# main.net
KiCad netlist of a schematic drawn in Altium Designer
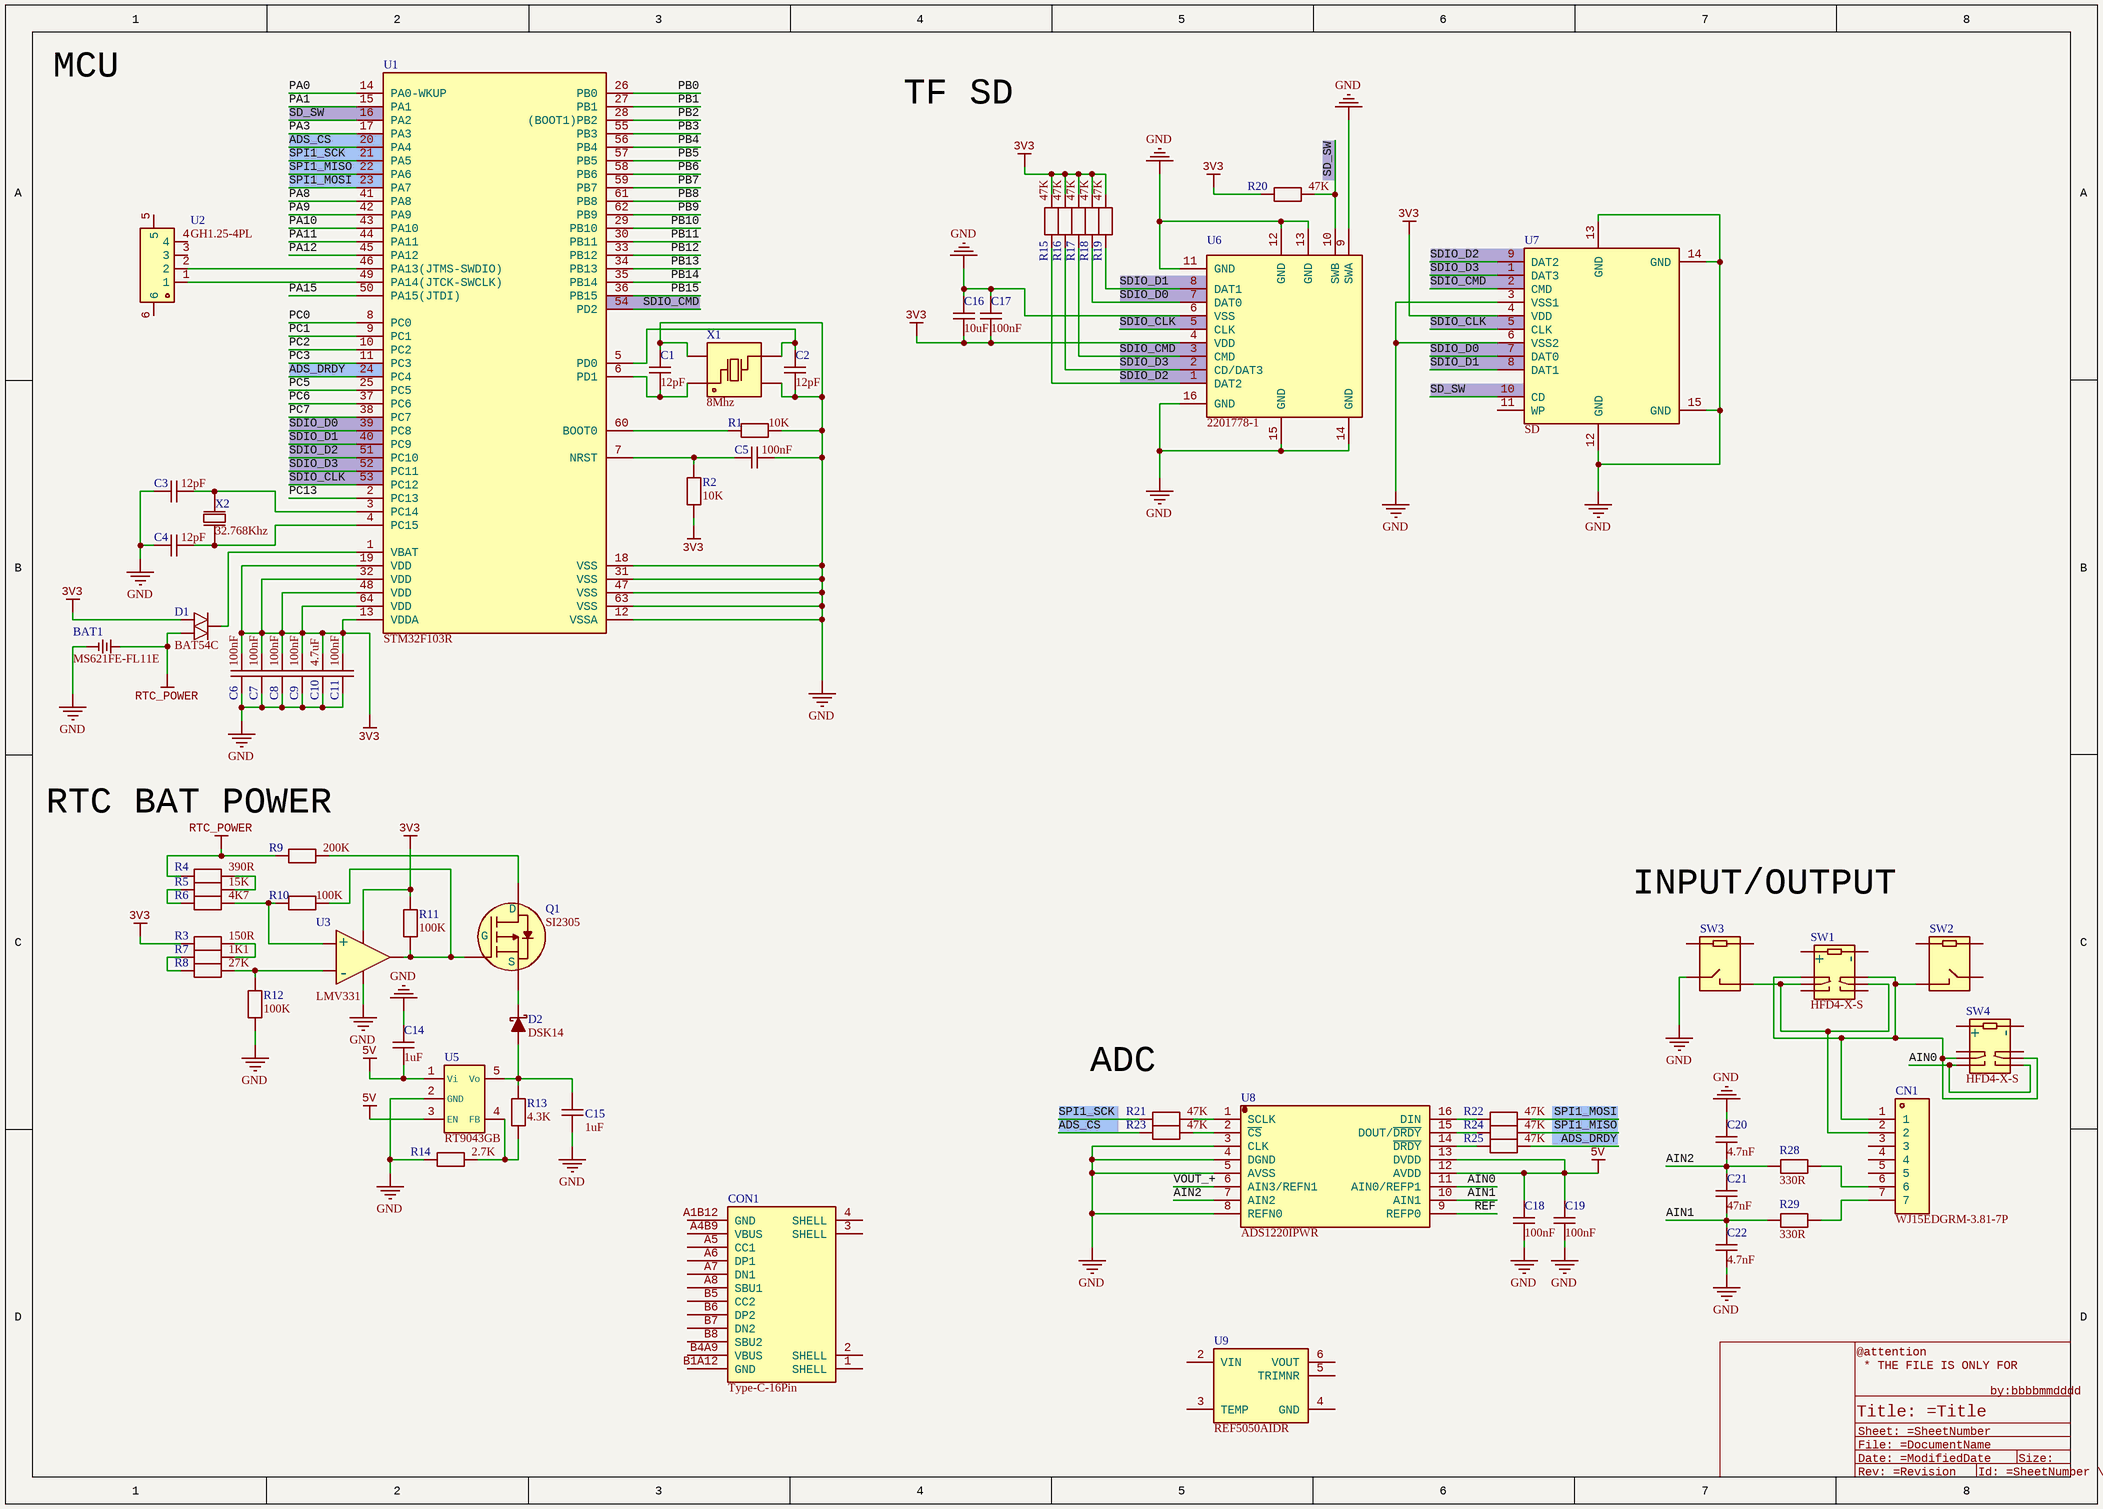
[diagram p0: main.SchDoc]

(export (version "E")
  (design (tool "Eeschema 10.0.6"))
  (components
    (comp (ref "BAT1")
      (value "MS621FE-FL11E")
      (footprint "SMD_FL11E")
      (libsource (lib "STM32") (part "MS621FE-FL11E"))
    )
    (comp (ref "C1") (value "12pF") (footprint "C_0402") (libsource (lib "STM32") (part "C_MLCC")))
    (comp (ref "C2") (value "12pF") (footprint "C_0402") (libsource (lib "STM32") (part "C_MLCC")))
    (comp (ref "C3") (value "12pF") (footprint "C_0402") (libsource (lib "STM32") (part "C_MLCC")))
    (comp (ref "C4") (value "12pF") (footprint "C_0402") (libsource (lib "STM32") (part "C_MLCC")))
    (comp (ref "C5") (value "100nF") (footprint "C_0402") (libsource (lib "STM32") (part "C_MLCC")))
    (comp (ref "C6") (value "100nF") (footprint "C_0603") (libsource (lib "STM32") (part "C_MLCC")))
    (comp (ref "C7") (value "100nF") (footprint "C_0603") (libsource (lib "STM32") (part "C_MLCC")))
    (comp (ref "C8") (value "100nF") (footprint "C_0603") (libsource (lib "STM32") (part "C_MLCC")))
    (comp (ref "C9") (value "100nF") (footprint "C_0603") (libsource (lib "STM32") (part "C_MLCC")))
    (comp (ref "C10") (value "4.7uF") (footprint "C_0603") (libsource (lib "STM32") (part "C_MLCC")))
    (comp (ref "C11") (value "100nF") (footprint "C_0603") (libsource (lib "STM32") (part "C_MLCC")))
    (comp (ref "C14") (value "1uF") (footprint "C_0603") (libsource (lib "STM32") (part "C_MLCC")))
    (comp (ref "C15") (value "1uF") (footprint "C_0603") (libsource (lib "STM32") (part "C_MLCC")))
    (comp (ref "C16") (value "10uF") (footprint "C_0603") (libsource (lib "STM32") (part "C_MLCC")))
    (comp (ref "C17") (value "100nF") (footprint "C_0402") (libsource (lib "STM32") (part "C_MLCC")))
    (comp (ref "C18") (value "100nF") (footprint "C_0805") (libsource (lib "STM32") (part "C_MLCC")))
    (comp (ref "C19") (value "100nF") (footprint "C_0805") (libsource (lib "STM32") (part "C_MLCC")))
    (comp (ref "C20") (value "4.7nF") (footprint "C_0603") (libsource (lib "STM32") (part "C_MLCC")))
    (comp (ref "C21") (value "47nF") (footprint "C_0603") (libsource (lib "STM32") (part "C_MLCC")))
    (comp (ref "C22") (value "4.7nF") (footprint "C_0603") (libsource (lib "STM32") (part "C_MLCC")))
    (comp (ref "CN1")
      (value "WJ15EDGRM-3.81-7P")
      (footprint "WJ15EDGRM-3.81-7P")
      (libsource (lib "STM32") (part "WJ15EDGRM-3.81-7P"))
    )
    (comp (ref "CON1")
      (value "Type-C-16Pin")
      (footprint "Type-C-16Pin")
      (libsource (lib "STM32") (part "Type-C-16Pin"))
    )
    (comp (ref "D1")
      (value "BAT54C")
      (footprint "SOT-23")
      (description "SOT-23")
      (libsource (lib "STM32") (part "BAT54C"))
    )
    (comp (ref "D2") (value "DSK14") (footprint "SOD-123FL") (libsource (lib "STM32") (part "DSK14")))
    (comp (ref "Q1")
      (value "SI2305")
      (footprint "SOT-23")
      (description "p-mos")
      (libsource (lib "STM32") (part "SI2305"))
    )
    (comp (ref "R1") (value "10K") (footprint "R_0402") (libsource (lib "STM32") (part "R_SMD")))
    (comp (ref "R2") (value "10K") (footprint "R_0402") (libsource (lib "STM32") (part "R_SMD")))
    (comp (ref "R3") (value "150R") (footprint "R_0402") (libsource (lib "STM32") (part "R_SMD")))
    (comp (ref "R4") (value "390R") (footprint "R_0402") (libsource (lib "STM32") (part "R_SMD")))
    (comp (ref "R5") (value "15K") (footprint "R_0402") (libsource (lib "STM32") (part "R_SMD")))
    (comp (ref "R6") (value "4K7") (footprint "R_0402") (libsource (lib "STM32") (part "R_SMD")))
    (comp (ref "R7") (value "1K1") (footprint "R_0402") (libsource (lib "STM32") (part "R_SMD")))
    (comp (ref "R8") (value "27K") (footprint "R_0402") (libsource (lib "STM32") (part "R_SMD")))
    (comp (ref "R9") (value "200K") (footprint "R_0402") (libsource (lib "STM32") (part "R_SMD")))
    (comp (ref "R10") (value "100K") (footprint "R_0402") (libsource (lib "STM32") (part "R_SMD")))
    (comp (ref "R11") (value "100K") (footprint "R_0402") (libsource (lib "STM32") (part "R_SMD")))
    (comp (ref "R12") (value "100K") (footprint "R_0402") (libsource (lib "STM32") (part "R_SMD")))
    (comp (ref "R13") (value "4.3K") (footprint "R_0402") (libsource (lib "STM32") (part "R_SMD")))
    (comp (ref "R14") (value "2.7K") (footprint "R_0402") (libsource (lib "STM32") (part "R_SMD")))
    (comp (ref "R15") (value "47K") (footprint "R_0402") (libsource (lib "STM32") (part "R_SMD")))
    (comp (ref "R16") (value "47K") (footprint "R_0402") (libsource (lib "STM32") (part "R_SMD")))
    (comp (ref "R17") (value "47K") (footprint "R_0402") (libsource (lib "STM32") (part "R_SMD")))
    (comp (ref "R18") (value "47K") (footprint "R_0402") (libsource (lib "STM32") (part "R_SMD")))
    (comp (ref "R19") (value "47K") (footprint "R_0402") (libsource (lib "STM32") (part "R_SMD")))
    (comp (ref "R20") (value "47K") (footprint "R_0402") (libsource (lib "STM32") (part "R_SMD")))
    (comp (ref "R21") (value "47K") (footprint "R_0402") (libsource (lib "STM32") (part "R_SMD")))
    (comp (ref "R22") (value "47K") (footprint "R_0402") (libsource (lib "STM32") (part "R_SMD")))
    (comp (ref "R23") (value "47K") (footprint "R_0402") (libsource (lib "STM32") (part "R_SMD")))
    (comp (ref "R24") (value "47K") (footprint "R_0402") (libsource (lib "STM32") (part "R_SMD")))
    (comp (ref "R25") (value "47K") (footprint "R_0402") (libsource (lib "STM32") (part "R_SMD")))
    (comp (ref "R28") (value "330R") (footprint "R_0603") (libsource (lib "STM32") (part "R_SMD")))
    (comp (ref "R29") (value "330R") (footprint "R_0603") (libsource (lib "STM32") (part "R_SMD")))
    (comp (ref "SW1")
      (value "HFD4-X-S")
      (footprint "HFD4-X-S")
      (description "继电器")
      (libsource (lib "STM32") (part "HFD4-X-S"))
    )
    (comp (ref "SW2")
      (value "HF32FV-16/5-HLTF(590)")
      (footprint "HF32FV-16/5-HLTF(590)")
      (description "继电器")
      (libsource (lib "STM32") (part "HF32FV-16/5-HLTF(590)"))
    )
    (comp (ref "SW3")
      (value "HF32FV-16/5-HLTF(590)")
      (footprint "HF32FV-16/5-HLTF(590)")
      (description "继电器")
      (libsource (lib "") (part "HF32FV-16/5-HLTF(590)_1"))
    )
    (comp (ref "SW4")
      (value "HFD4-X-S")
      (footprint "HFD4-X-S")
      (description "继电器")
      (libsource (lib "STM32") (part "HFD4-X-S"))
    )
    (comp (ref "U1")
      (value "STM32F103R")
      (footprint "LQFP_64")
      (description "64-pin LQFP")
      (libsource (lib "STM32") (part "STM32F103Rx"))
    )
    (comp (ref "U2")
      (value "GH1.25-4PL")
      (footprint "GH1.25-4PL")
      (libsource (lib "STM32") (part "GH1.25-4PL"))
    )
    (comp (ref "U3")
      (value "LMV331")
      (footprint "SOT-23-5P")
      (description "LMV331IDBVR")
      (libsource (lib "STM32") (part "LMV331IDBVR"))
    )
    (comp (ref "U5")
      (value "RT9043GB")
      (footprint "SOT-23-5P")
      (description "LDO")
      (libsource (lib "STM32") (part "RT9043GB"))
    )
    (comp (ref "U6")
      (value "2201778-1")
      (footprint "2201778-1")
      (description "TF卡槽")
      (libsource (lib "STM32") (part "2201778-1"))
    )
    (comp (ref "U7")
      (value "SD")
      (footprint "SMD_SD-102")
      (description "长体SD卡槽")
      (libsource (lib "STM32") (part "长体SD卡槽"))
    )
    (comp (ref "U8")
      (value "ADS1220IPWR")
      (footprint "TSSOP-16")
      (description "24Bit ADC")
      (libsource (lib "STM32") (part "ADS1220IPWR"))
    )
    (comp (ref "U9")
      (value "REF5050AIDR")
      (footprint "SOIC-8")
      (libsource (lib "STM32") (part "REF5050AIDR"))
    )
    (comp (ref "X1")
      (value "8Mhz")
      (footprint "SMD3225-4P")
      (libsource (lib "STM32") (part "Crystal_SMD3225-4P"))
    )
    (comp (ref "X2")
      (value "32.768Khz")
      (footprint "SMD3215-2P")
      (libsource (lib "STM32") (part "Crystal_3215-2P"))
    )
  )
  (nets
    (net (code "1") (name "/ADS_CS") (class "Default")
      (node (ref "R23") (pin "1") (pinfunction "1_1") (pintype "passive"))
      (node (ref "U1") (pin "20") (pinfunction "PA4_20") (pintype "passive"))
    )
    (net (code "2") (name "/ADS_DRDY") (class "Default")
      (node (ref "R25") (pin "2") (pinfunction "2_2") (pintype "passive"))
      (node (ref "U1") (pin "24") (pinfunction "PC4_24") (pintype "passive"))
    )
    (net (code "3") (name "/AIN0") (class "Default")
      (node (ref "SW4") (pin "4") (pinfunction "4_4") (pintype "passive"))
      (node (ref "SW4") (pin "5") (pinfunction "5_5") (pintype "passive"))
      (node (ref "U8") (pin "11") (pinfunction "AIN0/REFP1_11") (pintype "passive"))
    )
    (net (code "4") (name "/AIN1") (class "Default")
      (node (ref "C21") (pin "2") (pinfunction "2_2") (pintype "passive"))
      (node (ref "C22") (pin "1") (pinfunction "1_1") (pintype "passive"))
      (node (ref "R29") (pin "1") (pinfunction "1_1") (pintype "passive"))
      (node (ref "U8") (pin "10") (pinfunction "AIN1_10") (pintype "passive"))
    )
    (net (code "5") (name "/AIN2") (class "Default")
      (node (ref "C20") (pin "2") (pinfunction "2_2") (pintype "passive"))
      (node (ref "C21") (pin "1") (pinfunction "1_1") (pintype "passive"))
      (node (ref "R28") (pin "1") (pinfunction "1_1") (pintype "passive"))
      (node (ref "U8") (pin "7") (pinfunction "AIN2_7") (pintype "passive"))
    )
    (net (code "6") (name "/PA0") (class "Default")
      (node (ref "U1") (pin "14") (pinfunction "PA0-WKUP_14") (pintype "passive"))
    )
    (net (code "7") (name "/PA1") (class "Default")
      (node (ref "U1") (pin "15") (pinfunction "PA1_15") (pintype "passive"))
    )
    (net (code "8") (name "/PA3") (class "Default")
      (node (ref "U1") (pin "17") (pinfunction "PA3_17") (pintype "passive"))
    )
    (net (code "9") (name "/PA8") (class "Default")
      (node (ref "U1") (pin "41") (pinfunction "PA8_41") (pintype "passive"))
    )
    (net (code "10") (name "/PA9") (class "Default")
      (node (ref "U1") (pin "42") (pinfunction "PA9_42") (pintype "passive"))
    )
    (net (code "11") (name "/PA10") (class "Default")
      (node (ref "U1") (pin "43") (pinfunction "PA10_43") (pintype "passive"))
    )
    (net (code "12") (name "/PA11") (class "Default")
      (node (ref "U1") (pin "44") (pinfunction "PA11_44") (pintype "passive"))
    )
    (net (code "13") (name "/PA12") (class "Default")
      (node (ref "U1") (pin "45") (pinfunction "PA12_45") (pintype "passive"))
    )
    (net (code "14") (name "/PA15") (class "Default")
      (node (ref "U1") (pin "50") (pinfunction "PA15(JTDI)_50") (pintype "passive"))
    )
    (net (code "15") (name "/PB0") (class "Default")
      (node (ref "U1") (pin "26") (pinfunction "PB0_26") (pintype "passive"))
    )
    (net (code "16") (name "/PB1") (class "Default")
      (node (ref "U1") (pin "27") (pinfunction "PB1_27") (pintype "passive"))
    )
    (net (code "17") (name "/PB2") (class "Default")
      (node (ref "U1") (pin "28") (pinfunction "(BOOT1)PB2_28") (pintype "passive"))
    )
    (net (code "18") (name "/PB3") (class "Default")
      (node (ref "U1") (pin "55") (pinfunction "PB3_55") (pintype "passive"))
    )
    (net (code "19") (name "/PB4") (class "Default")
      (node (ref "U1") (pin "56") (pinfunction "PB4_56") (pintype "passive"))
    )
    (net (code "20") (name "/PB5") (class "Default")
      (node (ref "U1") (pin "57") (pinfunction "PB5_57") (pintype "passive"))
    )
    (net (code "21") (name "/PB6") (class "Default")
      (node (ref "U1") (pin "58") (pinfunction "PB6_58") (pintype "passive"))
    )
    (net (code "22") (name "/PB7") (class "Default")
      (node (ref "U1") (pin "59") (pinfunction "PB7_59") (pintype "passive"))
    )
    (net (code "23") (name "/PB8") (class "Default")
      (node (ref "U1") (pin "61") (pinfunction "PB8_61") (pintype "passive"))
    )
    (net (code "24") (name "/PB9") (class "Default")
      (node (ref "U1") (pin "62") (pinfunction "PB9_62") (pintype "passive"))
    )
    (net (code "25") (name "/PB10") (class "Default")
      (node (ref "U1") (pin "29") (pinfunction "PB10_29") (pintype "passive"))
    )
    (net (code "26") (name "/PB11") (class "Default")
      (node (ref "U1") (pin "30") (pinfunction "PB11_30") (pintype "passive"))
    )
    (net (code "27") (name "/PB12") (class "Default")
      (node (ref "U1") (pin "33") (pinfunction "PB12_33") (pintype "passive"))
    )
    (net (code "28") (name "/PB13") (class "Default")
      (node (ref "U1") (pin "34") (pinfunction "PB13_34") (pintype "passive"))
    )
    (net (code "29") (name "/PB14") (class "Default")
      (node (ref "U1") (pin "35") (pinfunction "PB14_35") (pintype "passive"))
    )
    (net (code "30") (name "/PB15") (class "Default")
      (node (ref "U1") (pin "36") (pinfunction "PB15_36") (pintype "passive"))
    )
    (net (code "31") (name "/PC0") (class "Default")
      (node (ref "U1") (pin "8") (pinfunction "PC0_8") (pintype "passive"))
    )
    (net (code "32") (name "/PC1") (class "Default")
      (node (ref "U1") (pin "9") (pinfunction "PC1_9") (pintype "passive"))
    )
    (net (code "33") (name "/PC2") (class "Default")
      (node (ref "U1") (pin "10") (pinfunction "PC2_10") (pintype "passive"))
    )
    (net (code "34") (name "/PC3") (class "Default")
      (node (ref "U1") (pin "11") (pinfunction "PC3_11") (pintype "passive"))
    )
    (net (code "35") (name "/PC5") (class "Default")
      (node (ref "U1") (pin "25") (pinfunction "PC5_25") (pintype "passive"))
    )
    (net (code "36") (name "/PC6") (class "Default")
      (node (ref "U1") (pin "37") (pinfunction "PC6_37") (pintype "passive"))
    )
    (net (code "37") (name "/PC7") (class "Default")
      (node (ref "U1") (pin "38") (pinfunction "PC7_38") (pintype "passive"))
    )
    (net (code "38") (name "/PC13") (class "Default")
      (node (ref "U1") (pin "2") (pinfunction "PC13_2") (pintype "passive"))
    )
    (net (code "39") (name "/REF") (class "Default")
      (node (ref "U8") (pin "9") (pinfunction "REFP0_9") (pintype "passive"))
    )
    (net (code "40") (name "/SDIO_CLK") (class "Default")
      (node (ref "U1") (pin "53") (pinfunction "PC12_53") (pintype "passive"))
      (node (ref "U6") (pin "5") (pinfunction "CLK_5") (pintype "passive"))
      (node (ref "U7") (pin "5") (pinfunction "CLK_5") (pintype "passive"))
    )
    (net (code "41") (name "/SDIO_CMD") (class "Default")
      (node (ref "R17") (pin "1") (pinfunction "1_1") (pintype "passive"))
      (node (ref "U1") (pin "54") (pinfunction "PD2_54") (pintype "passive"))
      (node (ref "U6") (pin "3") (pinfunction "CMD_3") (pintype "passive"))
      (node (ref "U7") (pin "2") (pinfunction "CMD_2") (pintype "passive"))
    )
    (net (code "42") (name "/SDIO_D0") (class "Default")
      (node (ref "R18") (pin "1") (pinfunction "1_1") (pintype "passive"))
      (node (ref "U1") (pin "39") (pinfunction "PC8_39") (pintype "passive"))
      (node (ref "U6") (pin "7") (pinfunction "DAT0_7") (pintype "passive"))
      (node (ref "U7") (pin "7") (pinfunction "DAT0_7") (pintype "passive"))
    )
    (net (code "43") (name "/SDIO_D1") (class "Default")
      (node (ref "R19") (pin "1") (pinfunction "1_1") (pintype "passive"))
      (node (ref "U1") (pin "40") (pinfunction "PC9_40") (pintype "passive"))
      (node (ref "U6") (pin "8") (pinfunction "DAT1_8") (pintype "passive"))
      (node (ref "U7") (pin "8") (pinfunction "DAT1_8") (pintype "passive"))
    )
    (net (code "44") (name "/SDIO_D2") (class "Default")
      (node (ref "R15") (pin "1") (pinfunction "1_1") (pintype "passive"))
      (node (ref "U1") (pin "51") (pinfunction "PC10_51") (pintype "passive"))
      (node (ref "U6") (pin "1") (pinfunction "DAT2_1") (pintype "passive"))
      (node (ref "U7") (pin "9") (pinfunction "DAT2_9") (pintype "passive"))
    )
    (net (code "45") (name "/SDIO_D3") (class "Default")
      (node (ref "R16") (pin "1") (pinfunction "1_1") (pintype "passive"))
      (node (ref "U1") (pin "52") (pinfunction "PC11_52") (pintype "passive"))
      (node (ref "U6") (pin "2") (pinfunction "CD/DAT3_2") (pintype "passive"))
      (node (ref "U7") (pin "1") (pinfunction "DAT3_1") (pintype "passive"))
    )
    (net (code "46") (name "/SD_SW") (class "Default")
      (node (ref "R20") (pin "1") (pinfunction "1_1") (pintype "passive"))
      (node (ref "U1") (pin "16") (pinfunction "PA2_16") (pintype "passive"))
      (node (ref "U6") (pin "10") (pinfunction "SWB_10") (pintype "passive"))
      (node (ref "U7") (pin "10") (pinfunction "CD_10") (pintype "passive"))
    )
    (net (code "47") (name "/SPI1_MISO") (class "Default")
      (node (ref "R24") (pin "2") (pinfunction "2_2") (pintype "passive"))
      (node (ref "U1") (pin "22") (pinfunction "PA6_22") (pintype "passive"))
    )
    (net (code "48") (name "/SPI1_MOSI") (class "Default")
      (node (ref "R22") (pin "2") (pinfunction "2_2") (pintype "passive"))
      (node (ref "U1") (pin "23") (pinfunction "PA7_23") (pintype "passive"))
    )
    (net (code "49") (name "/SPI1_SCK") (class "Default")
      (node (ref "R21") (pin "1") (pinfunction "1_1") (pintype "passive"))
      (node (ref "U1") (pin "21") (pinfunction "PA5_21") (pintype "passive"))
    )
    (net (code "50") (name "/VOUT_+") (class "Default")
      (node (ref "U8") (pin "6") (pinfunction "AIN3/REFN1_6") (pintype "passive"))
    )
    (net (code "51") (name "3V3") (class "Default")
      (node (ref "C10") (pin "1") (pinfunction "1_1") (pintype "passive"))
      (node (ref "C11") (pin "1") (pinfunction "1_1") (pintype "passive"))
      (node (ref "C16") (pin "1") (pinfunction "1_1") (pintype "passive"))
      (node (ref "C17") (pin "1") (pinfunction "1_1") (pintype "passive"))
      (node (ref "C6") (pin "1") (pinfunction "1_1") (pintype "passive"))
      (node (ref "C7") (pin "1") (pinfunction "1_1") (pintype "passive"))
      (node (ref "C8") (pin "1") (pinfunction "1_1") (pintype "passive"))
      (node (ref "C9") (pin "1") (pinfunction "1_1") (pintype "passive"))
      (node (ref "D1") (pin "1") (pinfunction "1_1") (pintype "passive"))
      (node (ref "R11") (pin "2") (pinfunction "2_2") (pintype "passive"))
      (node (ref "R15") (pin "2") (pinfunction "2_2") (pintype "passive"))
      (node (ref "R16") (pin "2") (pinfunction "2_2") (pintype "passive"))
      (node (ref "R17") (pin "2") (pinfunction "2_2") (pintype "passive"))
      (node (ref "R18") (pin "2") (pinfunction "2_2") (pintype "passive"))
      (node (ref "R19") (pin "2") (pinfunction "2_2") (pintype "passive"))
      (node (ref "R2") (pin "2") (pinfunction "2_2") (pintype "passive"))
      (node (ref "R20") (pin "2") (pinfunction "2_2") (pintype "passive"))
      (node (ref "R3") (pin "1") (pinfunction "1_1") (pintype "passive"))
      (node (ref "U1") (pin "13") (pinfunction "VDDA_13") (pintype "passive"))
      (node (ref "U1") (pin "19") (pinfunction "VDD_19") (pintype "passive"))
      (node (ref "U1") (pin "32") (pinfunction "VDD_32") (pintype "passive"))
      (node (ref "U1") (pin "48") (pinfunction "VDD_48") (pintype "passive"))
      (node (ref "U1") (pin "64") (pinfunction "VDD_64") (pintype "passive"))
      (node (ref "U3") (pin "5") (pinfunction "5_5") (pintype "passive"))
      (node (ref "U6") (pin "4") (pinfunction "VDD_4") (pintype "passive"))
      (node (ref "U7") (pin "4") (pinfunction "VDD_4") (pintype "passive"))
    )
    (net (code "52") (name "5V") (class "Default")
      (node (ref "C14") (pin "2") (pinfunction "2_2") (pintype "passive"))
      (node (ref "C18") (pin "1") (pinfunction "1_1") (pintype "passive"))
      (node (ref "C19") (pin "1") (pinfunction "1_1") (pintype "passive"))
      (node (ref "U5") (pin "1") (pinfunction "Vi_1") (pintype "passive"))
      (node (ref "U5") (pin "3") (pinfunction "EN_3") (pintype "passive"))
      (node (ref "U8") (pin "12") (pinfunction "AVDD_12") (pintype "passive"))
      (node (ref "U8") (pin "13") (pinfunction "DVDD_13") (pintype "passive"))
    )
    (net (code "53") (name "GND") (class "Default")
      (node (ref "BAT1") (pin "2") (pinfunction "2_2") (pintype "passive"))
      (node (ref "C1") (pin "2") (pinfunction "2_2") (pintype "passive"))
      (node (ref "C10") (pin "2") (pinfunction "2_2") (pintype "passive"))
      (node (ref "C11") (pin "2") (pinfunction "2_2") (pintype "passive"))
      (node (ref "C14") (pin "1") (pinfunction "1_1") (pintype "passive"))
      (node (ref "C15") (pin "1") (pinfunction "1_1") (pintype "passive"))
      (node (ref "C16") (pin "2") (pinfunction "2_2") (pintype "passive"))
      (node (ref "C17") (pin "2") (pinfunction "2_2") (pintype "passive"))
      (node (ref "C18") (pin "2") (pinfunction "2_2") (pintype "passive"))
      (node (ref "C19") (pin "2") (pinfunction "2_2") (pintype "passive"))
      (node (ref "C2") (pin "1") (pinfunction "1_1") (pintype "passive"))
      (node (ref "C20") (pin "1") (pinfunction "1_1") (pintype "passive"))
      (node (ref "C22") (pin "2") (pinfunction "2_2") (pintype "passive"))
      (node (ref "C3") (pin "1") (pinfunction "1_1") (pintype "passive"))
      (node (ref "C4") (pin "1") (pinfunction "1_1") (pintype "passive"))
      (node (ref "C5") (pin "2") (pinfunction "2_2") (pintype "passive"))
      (node (ref "C6") (pin "2") (pinfunction "2_2") (pintype "passive"))
      (node (ref "C7") (pin "2") (pinfunction "2_2") (pintype "passive"))
      (node (ref "C8") (pin "2") (pinfunction "2_2") (pintype "passive"))
      (node (ref "C9") (pin "2") (pinfunction "2_2") (pintype "passive"))
      (node (ref "R1") (pin "2") (pinfunction "2_2") (pintype "passive"))
      (node (ref "R12") (pin "1") (pinfunction "1_1") (pintype "passive"))
      (node (ref "R14") (pin "2") (pinfunction "2_2") (pintype "passive"))
      (node (ref "SW3") (pin "4") (pinfunction "4_4") (pintype "passive"))
      (node (ref "U1") (pin "12") (pinfunction "VSSA_12") (pintype "passive"))
      (node (ref "U1") (pin "18") (pinfunction "VSS_18") (pintype "passive"))
      (node (ref "U1") (pin "31") (pinfunction "VSS_31") (pintype "passive"))
      (node (ref "U1") (pin "47") (pinfunction "VSS_47") (pintype "passive"))
      (node (ref "U1") (pin "63") (pinfunction "VSS_63") (pintype "passive"))
      (node (ref "U3") (pin "2") (pinfunction "2_2") (pintype "passive"))
      (node (ref "U5") (pin "2") (pinfunction "GND_2") (pintype "passive"))
      (node (ref "U6") (pin "11") (pinfunction "GND_11") (pintype "passive"))
      (node (ref "U6") (pin "12") (pinfunction "GND_12") (pintype "passive"))
      (node (ref "U6") (pin "13") (pinfunction "GND_13") (pintype "passive"))
      (node (ref "U6") (pin "14") (pinfunction "GND_14") (pintype "passive"))
      (node (ref "U6") (pin "15") (pinfunction "GND_15") (pintype "passive"))
      (node (ref "U6") (pin "16") (pinfunction "GND_16") (pintype "passive"))
      (node (ref "U6") (pin "6") (pinfunction "VSS_6") (pintype "passive"))
      (node (ref "U6") (pin "9") (pinfunction "SWA_9") (pintype "passive"))
      (node (ref "U7") (pin "12") (pinfunction "GND_12") (pintype "passive"))
      (node (ref "U7") (pin "13") (pinfunction "GND_13") (pintype "passive"))
      (node (ref "U7") (pin "14") (pinfunction "GND_14") (pintype "passive"))
      (node (ref "U7") (pin "15") (pinfunction "GND_15") (pintype "passive"))
      (node (ref "U7") (pin "3") (pinfunction "VSS1_3") (pintype "passive"))
      (node (ref "U7") (pin "6") (pinfunction "VSS2_6") (pintype "passive"))
      (node (ref "U8") (pin "3") (pinfunction "CLK_3") (pintype "passive"))
      (node (ref "U8") (pin "4") (pinfunction "DGND_4") (pintype "passive"))
      (node (ref "U8") (pin "5") (pinfunction "AVSS_5") (pintype "passive"))
      (node (ref "U8") (pin "8") (pinfunction "REFN0_8") (pintype "passive"))
      (node (ref "X1") (pin "2") (pinfunction "2_2") (pintype "passive"))
      (node (ref "X1") (pin "4") (pinfunction "4_4") (pintype "passive"))
    )
    (net (code "54") (name "Net-(CN1-Pad1)") (class "Default")
      (node (ref "CN1") (pin "1") (pinfunction "1_1") (pintype "passive"))
      (node (ref "SW1") (pin "2") (pinfunction "2_2") (pintype "passive"))
      (node (ref "SW1") (pin "7") (pinfunction "7_7") (pintype "passive"))
      (node (ref "SW2") (pin "3") (pinfunction "3_3") (pintype "passive"))
      (node (ref "SW4") (pin "3") (pinfunction "3_3") (pintype "passive"))
      (node (ref "SW4") (pin "6") (pinfunction "6_6") (pintype "passive"))
    )
    (net (code "55") (name "Net-(CN1-Pad2)") (class "Default")
      (node (ref "CN1") (pin "2") (pinfunction "2_2") (pintype "passive"))
      (node (ref "SW1") (pin "3") (pinfunction "3_3") (pintype "passive"))
      (node (ref "SW1") (pin "6") (pinfunction "6_6") (pintype "passive"))
      (node (ref "SW3") (pin "3") (pinfunction "3_3") (pintype "passive"))
    )
    (net (code "56") (name "Net-(CN1-Pad6)") (class "Default")
      (node (ref "CN1") (pin "6") (pinfunction "6_6") (pintype "passive"))
      (node (ref "R28") (pin "2") (pinfunction "2_2") (pintype "passive"))
    )
    (net (code "57") (name "Net-(CN1-Pad7)") (class "Default")
      (node (ref "CN1") (pin "7") (pinfunction "7_7") (pintype "passive"))
      (node (ref "R29") (pin "2") (pinfunction "2_2") (pintype "passive"))
    )
    (net (code "58") (name "Net-(Q1-D)") (class "Default")
      (node (ref "Q1") (pin "3") (pinfunction "D_3") (pintype "passive"))
      (node (ref "R9") (pin "1") (pinfunction "1_1") (pintype "passive"))
    )
    (net (code "59") (name "Net-(Q1-G)") (class "Default")
      (node (ref "Q1") (pin "1") (pinfunction "G_1") (pintype "passive"))
      (node (ref "R10") (pin "1") (pinfunction "1_1") (pintype "passive"))
      (node (ref "R11") (pin "1") (pinfunction "1_1") (pintype "passive"))
      (node (ref "U3") (pin "4") (pinfunction "4_4") (pintype "passive"))
    )
    (net (code "60") (name "Net-(Q1-S)") (class "Default")
      (node (ref "D2") (pin "1") (pinfunction "1_1") (pintype "passive"))
      (node (ref "Q1") (pin "2") (pinfunction "S_2") (pintype "passive"))
    )
    (net (code "61") (name "Net-(R3-Pad2)") (class "Default")
      (node (ref "R3") (pin "2") (pinfunction "2_2") (pintype "passive"))
      (node (ref "R7") (pin "2") (pinfunction "2_2") (pintype "passive"))
    )
    (net (code "62") (name "Net-(R4-Pad2)") (class "Default")
      (node (ref "R4") (pin "2") (pinfunction "2_2") (pintype "passive"))
      (node (ref "R5") (pin "2") (pinfunction "2_2") (pintype "passive"))
    )
    (net (code "63") (name "Net-(R5-Pad1)") (class "Default")
      (node (ref "R5") (pin "1") (pinfunction "1_1") (pintype "passive"))
      (node (ref "R6") (pin "1") (pinfunction "1_1") (pintype "passive"))
    )
    (net (code "64") (name "Net-(R7-Pad1)") (class "Default")
      (node (ref "R7") (pin "1") (pinfunction "1_1") (pintype "passive"))
      (node (ref "R8") (pin "1") (pinfunction "1_1") (pintype "passive"))
    )
    (net (code "65") (name "Net-(R10-Pad2)") (class "Default")
      (node (ref "R10") (pin "2") (pinfunction "2_2") (pintype "passive"))
      (node (ref "R6") (pin "2") (pinfunction "2_2") (pintype "passive"))
      (node (ref "U3") (pin "1") (pinfunction "1_1") (pintype "passive"))
    )
    (net (code "66") (name "Net-(R12-Pad2)") (class "Default")
      (node (ref "R12") (pin "2") (pinfunction "2_2") (pintype "passive"))
      (node (ref "R8") (pin "2") (pinfunction "2_2") (pintype "passive"))
      (node (ref "U3") (pin "3") (pinfunction "3_3") (pintype "passive"))
    )
    (net (code "67") (name "Net-(U1-BOOT0)") (class "Default")
      (node (ref "R1") (pin "1") (pinfunction "1_1") (pintype "passive"))
      (node (ref "U1") (pin "60") (pinfunction "BOOT0_60") (pintype "passive"))
    )
    (net (code "68") (name "Net-(U1-NRST)") (class "Default")
      (node (ref "C5") (pin "1") (pinfunction "1_1") (pintype "passive"))
      (node (ref "R2") (pin "1") (pinfunction "1_1") (pintype "passive"))
      (node (ref "U1") (pin "7") (pinfunction "NRST_7") (pintype "passive"))
    )
    (net (code "69") (name "Net-(U1-PA13(JTMS-SWDIO))") (class "Default")
      (node (ref "U1") (pin "46") (pinfunction "PA13(JTMS-SWDIO)_46") (pintype "passive"))
      (node (ref "U2") (pin "2") (pinfunction "2_2") (pintype "passive"))
    )
    (net (code "70") (name "Net-(U1-PA14(JTCK-SWCLK))") (class "Default")
      (node (ref "U1") (pin "49") (pinfunction "PA14(JTCK-SWCLK)_49") (pintype "passive"))
      (node (ref "U2") (pin "1") (pinfunction "1_1") (pintype "passive"))
    )
    (net (code "71") (name "Net-(U1-PC14)") (class "Default")
      (node (ref "C3") (pin "2") (pinfunction "2_2") (pintype "passive"))
      (node (ref "U1") (pin "3") (pinfunction "PC14_3") (pintype "passive"))
      (node (ref "X2") (pin "2") (pinfunction "2_2") (pintype "passive"))
    )
    (net (code "72") (name "Net-(U1-PC15)") (class "Default")
      (node (ref "C4") (pin "2") (pinfunction "2_2") (pintype "passive"))
      (node (ref "U1") (pin "4") (pinfunction "PC15_4") (pintype "passive"))
      (node (ref "X2") (pin "1") (pinfunction "1_1") (pintype "passive"))
    )
    (net (code "73") (name "Net-(U1-PD0)") (class "Default")
      (node (ref "C2") (pin "2") (pinfunction "2_2") (pintype "passive"))
      (node (ref "U1") (pin "5") (pinfunction "PD0_5") (pintype "passive"))
      (node (ref "X1") (pin "3") (pinfunction "3_3") (pintype "passive"))
    )
    (net (code "74") (name "Net-(U1-PD1)") (class "Default")
      (node (ref "C1") (pin "1") (pinfunction "1_1") (pintype "passive"))
      (node (ref "U1") (pin "6") (pinfunction "PD1_6") (pintype "passive"))
      (node (ref "X1") (pin "1") (pinfunction "1_1") (pintype "passive"))
    )
    (net (code "75") (name "Net-(U1-VBAT)") (class "Default")
      (node (ref "D1") (pin "3") (pinfunction "3_3") (pintype "passive"))
      (node (ref "U1") (pin "1") (pinfunction "VBAT_1") (pintype "passive"))
    )
    (net (code "76") (name "Net-(U5-FB)") (class "Default")
      (node (ref "R13") (pin "1") (pinfunction "1_1") (pintype "passive"))
      (node (ref "R14") (pin "1") (pinfunction "1_1") (pintype "passive"))
      (node (ref "U5") (pin "4") (pinfunction "FB_4") (pintype "passive"))
    )
    (net (code "77") (name "Net-(U5-Vo)") (class "Default")
      (node (ref "C15") (pin "2") (pinfunction "2_2") (pintype "passive"))
      (node (ref "D2") (pin "2") (pinfunction "2_2") (pintype "passive"))
      (node (ref "R13") (pin "2") (pinfunction "2_2") (pintype "passive"))
      (node (ref "U5") (pin "5") (pinfunction "Vo_5") (pintype "passive"))
    )
    (net (code "78") (name "Net-(U8-DIN)") (class "Default")
      (node (ref "R22") (pin "1") (pinfunction "1_1") (pintype "passive"))
      (node (ref "U8") (pin "16") (pinfunction "DIN_16") (pintype "passive"))
    )
    (net (code "79") (name "Net-(U8-DOUT{slash}~{DRDY})") (class "Default")
      (node (ref "R24") (pin "1") (pinfunction "1_1") (pintype "passive"))
      (node (ref "U8") (pin "15") (pinfunction "DOUT/~{DRDY}_15") (pintype "passive"))
    )
    (net (code "80") (name "Net-(U8-SCLK)") (class "Default")
      (node (ref "R21") (pin "2") (pinfunction "2_2") (pintype "passive"))
      (node (ref "U8") (pin "1") (pinfunction "SCLK_1") (pintype "passive"))
    )
    (net (code "81") (name "Net-(U8-~{CS})") (class "Default")
      (node (ref "R23") (pin "2") (pinfunction "2_2") (pintype "passive"))
      (node (ref "U8") (pin "2") (pinfunction "~{CS}_2") (pintype "passive"))
    )
    (net (code "82") (name "Net-(U8-~{DRDY})") (class "Default")
      (node (ref "R25") (pin "1") (pinfunction "1_1") (pintype "passive"))
      (node (ref "U8") (pin "14") (pinfunction "~{DRDY}_14") (pintype "passive"))
    )
    (net (code "83") (name "RTC_POWER") (class "Default")
      (node (ref "BAT1") (pin "1") (pinfunction "1_1") (pintype "passive"))
      (node (ref "D1") (pin "2") (pinfunction "2_2") (pintype "passive"))
      (node (ref "R4") (pin "1") (pinfunction "1_1") (pintype "passive"))
      (node (ref "R9") (pin "2") (pinfunction "2_2") (pintype "passive"))
    )
    (net (code "84") (name "unconnected-(CN1-Pad3)") (class "Default")
      (node (ref "CN1") (pin "3") (pinfunction "3_3") (pintype "passive"))
    )
    (net (code "85") (name "unconnected-(CN1-Pad4)") (class "Default")
      (node (ref "CN1") (pin "4") (pinfunction "4_4") (pintype "passive"))
    )
    (net (code "86") (name "unconnected-(CN1-Pad5)") (class "Default")
      (node (ref "CN1") (pin "5") (pinfunction "5_5") (pintype "passive"))
    )
    (net (code "87") (name "unconnected-(CON1-CC1-PadA5)") (class "Default")
      (node (ref "CON1") (pin "A5") (pinfunction "CC1_A5") (pintype "passive"))
    )
    (net (code "88") (name "unconnected-(CON1-CC2-PadB5)") (class "Default")
      (node (ref "CON1") (pin "B5") (pinfunction "CC2_B5") (pintype "passive"))
    )
    (net (code "89") (name "unconnected-(CON1-DN1-PadA7)") (class "Default")
      (node (ref "CON1") (pin "A7") (pinfunction "DN1_A7") (pintype "passive"))
    )
    (net (code "90") (name "unconnected-(CON1-DN2-PadB7)") (class "Default")
      (node (ref "CON1") (pin "B7") (pinfunction "DN2_B7") (pintype "passive"))
    )
    (net (code "91") (name "unconnected-(CON1-DP1-PadA6)") (class "Default")
      (node (ref "CON1") (pin "A6") (pinfunction "DP1_A6") (pintype "passive"))
    )
    (net (code "92") (name "unconnected-(CON1-DP2-PadB6)") (class "Default")
      (node (ref "CON1") (pin "B6") (pinfunction "DP2_B6") (pintype "passive"))
    )
    (net (code "93") (name "unconnected-(CON1-GND-PadA1B12)") (class "Default")
      (node (ref "CON1") (pin "A1B12") (pinfunction "GND_A1B12") (pintype "passive"))
    )
    (net (code "94") (name "unconnected-(CON1-GND-PadB1A12)") (class "Default")
      (node (ref "CON1") (pin "B1A12") (pinfunction "GND_B1A12") (pintype "passive"))
    )
    (net (code "95") (name "unconnected-(CON1-SBU1-PadA8)") (class "Default")
      (node (ref "CON1") (pin "A8") (pinfunction "SBU1_A8") (pintype "passive"))
    )
    (net (code "96") (name "unconnected-(CON1-SBU2-PadB8)") (class "Default")
      (node (ref "CON1") (pin "B8") (pinfunction "SBU2_B8") (pintype "passive"))
    )
    (net (code "97") (name "unconnected-(CON1-SHELL-Pad1)") (class "Default")
      (node (ref "CON1") (pin "1") (pinfunction "SHELL_1") (pintype "passive"))
    )
    (net (code "98") (name "unconnected-(CON1-SHELL-Pad2)") (class "Default")
      (node (ref "CON1") (pin "2") (pinfunction "SHELL_2") (pintype "passive"))
    )
    (net (code "99") (name "unconnected-(CON1-SHELL-Pad3)") (class "Default")
      (node (ref "CON1") (pin "3") (pinfunction "SHELL_3") (pintype "passive"))
    )
    (net (code "100") (name "unconnected-(CON1-SHELL-Pad4)") (class "Default")
      (node (ref "CON1") (pin "4") (pinfunction "SHELL_4") (pintype "passive"))
    )
    (net (code "101") (name "unconnected-(CON1-VBUS-PadA4B9)") (class "Default")
      (node (ref "CON1") (pin "A4B9") (pinfunction "VBUS_A4B9") (pintype "passive"))
    )
    (net (code "102") (name "unconnected-(CON1-VBUS-PadB4A9)") (class "Default")
      (node (ref "CON1") (pin "B4A9") (pinfunction "VBUS_B4A9") (pintype "passive"))
    )
    (net (code "103") (name "unconnected-(SW1-Pad1)") (class "Default")
      (node (ref "SW1") (pin "1") (pinfunction "1_1") (pintype "passive"))
    )
    (net (code "104") (name "unconnected-(SW1-Pad4)") (class "Default")
      (node (ref "SW1") (pin "4") (pinfunction "4_4") (pintype "passive"))
    )
    (net (code "105") (name "unconnected-(SW1-Pad5)") (class "Default")
      (node (ref "SW1") (pin "5") (pinfunction "5_5") (pintype "passive"))
    )
    (net (code "106") (name "unconnected-(SW1-Pad8)") (class "Default")
      (node (ref "SW1") (pin "8") (pinfunction "8_8") (pintype "passive"))
    )
    (net (code "107") (name "unconnected-(SW2-Pad1)") (class "Default")
      (node (ref "SW2") (pin "1") (pinfunction "1_1") (pintype "passive"))
    )
    (net (code "108") (name "unconnected-(SW2-Pad2)") (class "Default")
      (node (ref "SW2") (pin "2") (pinfunction "2_2") (pintype "passive"))
    )
    (net (code "109") (name "unconnected-(SW2-Pad4)") (class "Default")
      (node (ref "SW2") (pin "4") (pinfunction "4_4") (pintype "passive"))
    )
    (net (code "110") (name "unconnected-(SW3-Pad1)") (class "Default")
      (node (ref "SW3") (pin "1") (pinfunction "1_1") (pintype "passive"))
    )
    (net (code "111") (name "unconnected-(SW3-Pad2)") (class "Default")
      (node (ref "SW3") (pin "2") (pinfunction "2_2") (pintype "passive"))
    )
    (net (code "112") (name "unconnected-(SW4-Pad1)") (class "Default")
      (node (ref "SW4") (pin "1") (pinfunction "1_1") (pintype "passive"))
    )
    (net (code "113") (name "unconnected-(SW4-Pad2)") (class "Default")
      (node (ref "SW4") (pin "2") (pinfunction "2_2") (pintype "passive"))
    )
    (net (code "114") (name "unconnected-(SW4-Pad7)") (class "Default")
      (node (ref "SW4") (pin "7") (pinfunction "7_7") (pintype "passive"))
    )
    (net (code "115") (name "unconnected-(SW4-Pad8)") (class "Default")
      (node (ref "SW4") (pin "8") (pinfunction "8_8") (pintype "passive"))
    )
    (net (code "116") (name "unconnected-(U2-Pad3)") (class "Default")
      (node (ref "U2") (pin "3") (pinfunction "3_3") (pintype "passive"))
    )
    (net (code "117") (name "unconnected-(U2-Pad4)") (class "Default")
      (node (ref "U2") (pin "4") (pinfunction "4_4") (pintype "passive"))
    )
    (net (code "118") (name "unconnected-(U2-Pad5)") (class "Default")
      (node (ref "U2") (pin "5") (pinfunction "5_5") (pintype "passive"))
    )
    (net (code "119") (name "unconnected-(U2-Pad6)") (class "Default")
      (node (ref "U2") (pin "6") (pinfunction "6_6") (pintype "passive"))
    )
    (net (code "120") (name "unconnected-(U7-WP-Pad11)") (class "Default")
      (node (ref "U7") (pin "11") (pinfunction "WP_11") (pintype "passive"))
    )
    (net (code "121") (name "unconnected-(U9-GND-Pad4)") (class "Default")
      (node (ref "U9") (pin "4") (pinfunction "GND_4") (pintype "passive"))
    )
    (net (code "122") (name "unconnected-(U9-TEMP-Pad3)") (class "Default")
      (node (ref "U9") (pin "3") (pinfunction "TEMP_3") (pintype "passive"))
    )
    (net (code "123") (name "unconnected-(U9-TRIMNR-Pad5)") (class "Default")
      (node (ref "U9") (pin "5") (pinfunction "TRIMNR_5") (pintype "passive"))
    )
    (net (code "124") (name "unconnected-(U9-VIN-Pad2)") (class "Default")
      (node (ref "U9") (pin "2") (pinfunction "VIN_2") (pintype "passive"))
    )
    (net (code "125") (name "unconnected-(U9-VOUT-Pad6)") (class "Default")
      (node (ref "U9") (pin "6") (pinfunction "VOUT_6") (pintype "passive"))
    )
  )
)
